# Wigglagotchi.net
KiCad netlist of a schematic drawn in Altium Designer
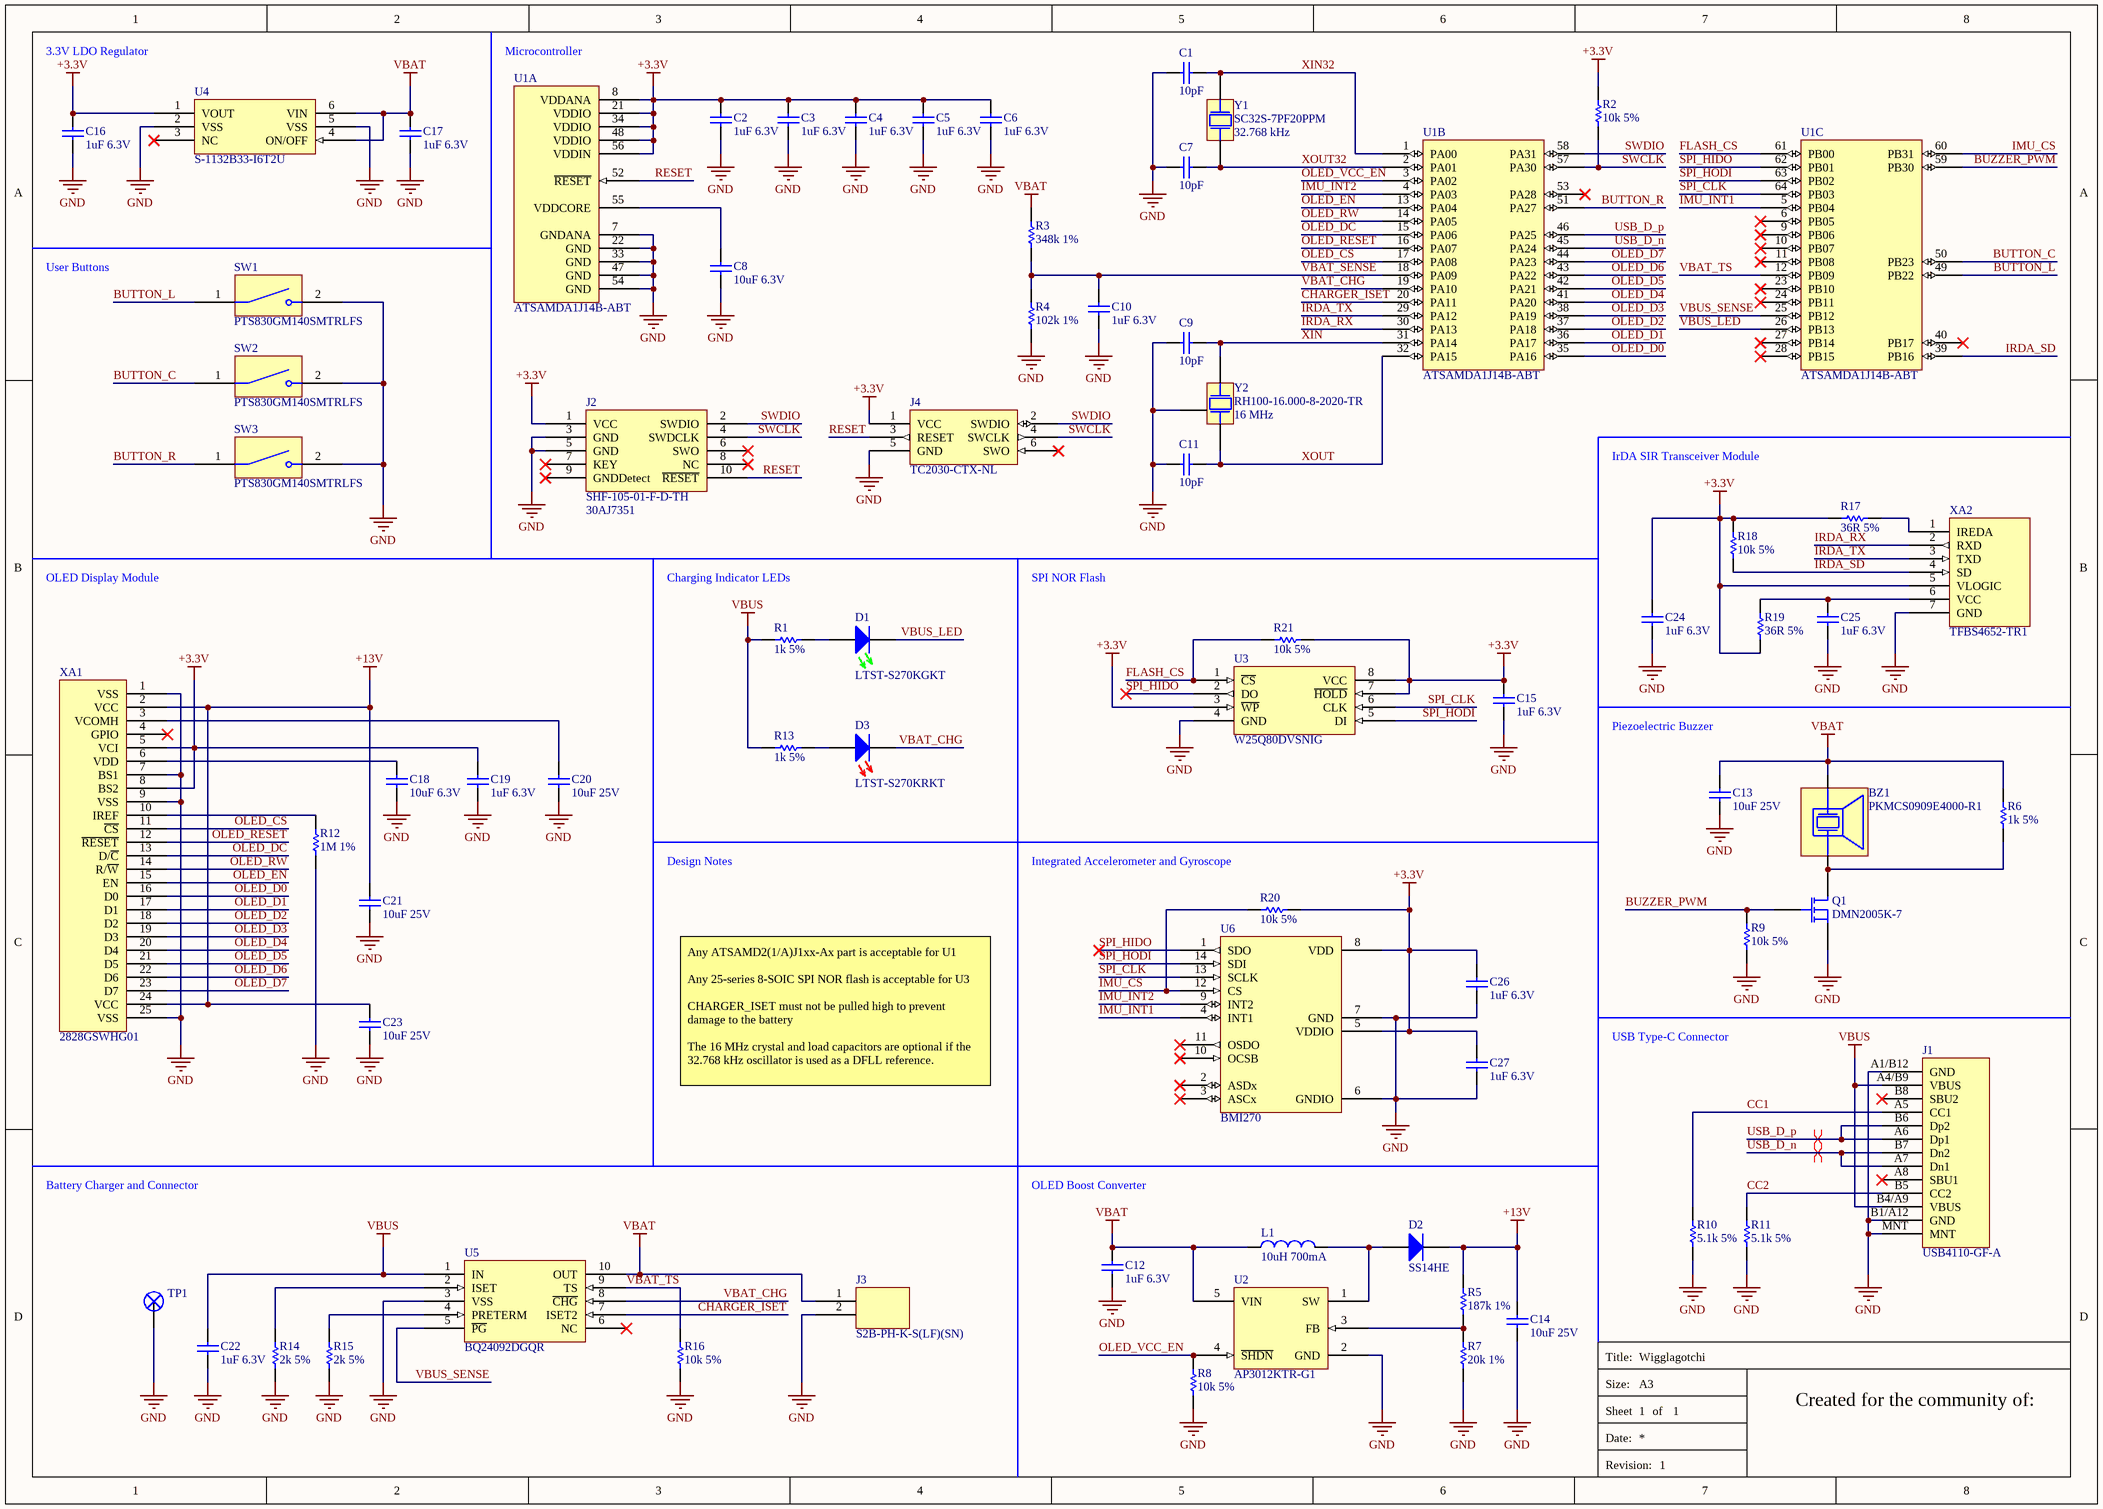
[diagram p0: Wigglagotchi.SchDoc]

(export (version "E")
  (design (tool "Eeschema 10.0.6"))
  (components
    (comp (ref "BZ1")
      (value "PKMCS0909E4000-R1")
      (footprint "PKMCS0909E4000-R1")
      (description "Buzzers Transducer, Externally Driven Piezo 1.5 V 4kHz 65dB @ 1.5V, 10cm Surface Mount Solder Pads")
      (libsource (lib "symbols") (part "PKMCS0909E4000-R1"))
    )
    (comp (ref "C1")
      (value "10pF")
      (footprint "GRM155 0402 Capacitor")
      (description "10 pF ±2% 50V Ceramic Capacitor C0G, NP0 0402 (1005 Metric)")
      (fields (field (name "Comment") "GCM1555C1H100GA16D"))
      (libsource (lib "symbols") (part "GCM1555C1H100GA16D"))
    )
    (comp (ref "C2")
      (value "1uF 6.3V")
      (footprint "GRM155 0402 Capacitor")
      (description "1 µF ±20% 6.3V Ceramic Capacitor X5R 0402 (1005 Metric)")
      (fields (field (name "Comment") "GRM153R60J105ME15D"))
      (libsource (lib "symbols") (part "GRM153R60J105ME15D"))
    )
    (comp (ref "C3")
      (value "1uF 6.3V")
      (footprint "GRM155 0402 Capacitor")
      (description "1 µF ±20% 6.3V Ceramic Capacitor X5R 0402 (1005 Metric)")
      (fields (field (name "Comment") "GRM153R60J105ME15D"))
      (libsource (lib "symbols") (part "GRM153R60J105ME15D"))
    )
    (comp (ref "C4")
      (value "1uF 6.3V")
      (footprint "GRM155 0402 Capacitor")
      (description "1 µF ±20% 6.3V Ceramic Capacitor X5R 0402 (1005 Metric)")
      (fields (field (name "Comment") "GRM153R60J105ME15D"))
      (libsource (lib "symbols") (part "GRM153R60J105ME15D"))
    )
    (comp (ref "C5")
      (value "1uF 6.3V")
      (footprint "GRM155 0402 Capacitor")
      (description "1 µF ±20% 6.3V Ceramic Capacitor X5R 0402 (1005 Metric)")
      (fields (field (name "Comment") "GRM153R60J105ME15D"))
      (libsource (lib "symbols") (part "GRM153R60J105ME15D"))
    )
    (comp (ref "C6")
      (value "1uF 6.3V")
      (footprint "GRM155 0402 Capacitor")
      (description "1 µF ±20% 6.3V Ceramic Capacitor X5R 0402 (1005 Metric)")
      (fields (field (name "Comment") "GRM153R60J105ME15D"))
      (libsource (lib "symbols") (part "GRM153R60J105ME15D"))
    )
    (comp (ref "C7")
      (value "10pF")
      (footprint "GRM155 0402 Capacitor")
      (description "10 pF ±2% 50V Ceramic Capacitor C0G, NP0 0402 (1005 Metric)")
      (fields (field (name "Comment") "GCM1555C1H100GA16D"))
      (libsource (lib "symbols") (part "GCM1555C1H100GA16D"))
    )
    (comp (ref "C8")
      (value "10uF 6.3V")
      (footprint "GRM155 0402 Capacitor")
      (description "10 µF ±20% 6.3V Ceramic Capacitor X5R 0402 (1005 Metric)")
      (fields (field (name "Comment") "GRM155R60J106ME15D"))
      (libsource (lib "symbols") (part "GRM155R60J106ME15D"))
    )
    (comp (ref "C9")
      (value "10pF")
      (footprint "GRM155 0402 Capacitor")
      (description "10 pF ±2% 50V Ceramic Capacitor C0G, NP0 0402 (1005 Metric)")
      (fields (field (name "Comment") "GCM1555C1H100GA16D"))
      (libsource (lib "symbols") (part "GCM1555C1H100GA16D"))
    )
    (comp (ref "C10")
      (value "1uF 6.3V")
      (footprint "GRM155 0402 Capacitor")
      (description "1 µF ±20% 6.3V Ceramic Capacitor X5R 0402 (1005 Metric)")
      (fields (field (name "Comment") "GRM153R60J105ME15D"))
      (libsource (lib "symbols") (part "GRM153R60J105ME15D"))
    )
    (comp (ref "C11")
      (value "10pF")
      (footprint "GRM155 0402 Capacitor")
      (description "10 pF ±2% 50V Ceramic Capacitor C0G, NP0 0402 (1005 Metric)")
      (fields (field (name "Comment") "GCM1555C1H100GA16D"))
      (libsource (lib "symbols") (part "GCM1555C1H100GA16D"))
    )
    (comp (ref "C12")
      (value "1uF 6.3V")
      (footprint "GRM155 0402 Capacitor")
      (description "1 µF ±20% 6.3V Ceramic Capacitor X5R 0402 (1005 Metric)")
      (fields (field (name "Comment") "GRM153R60J105ME15D"))
      (libsource (lib "symbols") (part "GRM153R60J105ME15D"))
    )
    (comp (ref "C13")
      (value "10uF 25V")
      (footprint "GRM21 0805 Capacitor")
      (description "10 µF ±10% 25V Ceramic Capacitor X5R 0805 (2012 Metric)")
      (fields (field (name "Comment") "GRM21BR61E106KA73K"))
      (libsource (lib "symbols") (part "GRM21BR61E106KA73K"))
    )
    (comp (ref "C14")
      (value "10uF 25V")
      (footprint "GRM21 0805 Capacitor")
      (description "10 µF ±10% 25V Ceramic Capacitor X5R 0805 (2012 Metric)")
      (fields (field (name "Comment") "GRM21BR61E106KA73K"))
      (libsource (lib "symbols") (part "GRM21BR61E106KA73K"))
    )
    (comp (ref "C15")
      (value "1uF 6.3V")
      (footprint "GRM155 0402 Capacitor")
      (description "1 µF ±20% 6.3V Ceramic Capacitor X5R 0402 (1005 Metric)")
      (fields (field (name "Comment") "GRM153R60J105ME15D"))
      (libsource (lib "symbols") (part "GRM153R60J105ME15D"))
    )
    (comp (ref "C16")
      (value "1uF 6.3V")
      (footprint "GRM155 0402 Capacitor")
      (description "1 µF ±20% 6.3V Ceramic Capacitor X5R 0402 (1005 Metric)")
      (fields (field (name "Comment") "GRM153R60J105ME15D"))
      (libsource (lib "symbols") (part "GRM153R60J105ME15D"))
    )
    (comp (ref "C17")
      (value "1uF 6.3V")
      (footprint "GRM155 0402 Capacitor")
      (description "1 µF ±20% 6.3V Ceramic Capacitor X5R 0402 (1005 Metric)")
      (fields (field (name "Comment") "GRM153R60J105ME15D"))
      (libsource (lib "symbols") (part "GRM153R60J105ME15D"))
    )
    (comp (ref "C18")
      (value "10uF 6.3V")
      (footprint "GRM155 0402 Capacitor")
      (description "10 µF ±20% 6.3V Ceramic Capacitor X5R 0402 (1005 Metric)")
      (fields (field (name "Comment") "GRM155R60J106ME15D"))
      (libsource (lib "symbols") (part "GRM155R60J106ME15D"))
    )
    (comp (ref "C19")
      (value "1uF 6.3V")
      (footprint "GRM155 0402 Capacitor")
      (description "1 µF ±20% 6.3V Ceramic Capacitor X5R 0402 (1005 Metric)")
      (fields (field (name "Comment") "GRM153R60J105ME15D"))
      (libsource (lib "symbols") (part "GRM153R60J105ME15D"))
    )
    (comp (ref "C20")
      (value "10uF 25V")
      (footprint "GRM21 0805 Capacitor")
      (description "10 µF ±10% 25V Ceramic Capacitor X5R 0805 (2012 Metric)")
      (fields (field (name "Comment") "GRM21BR61E106KA73K"))
      (libsource (lib "symbols") (part "GRM21BR61E106KA73K"))
    )
    (comp (ref "C21")
      (value "10uF 25V")
      (footprint "GRM21 0805 Capacitor")
      (description "10 µF ±10% 25V Ceramic Capacitor X5R 0805 (2012 Metric)")
      (fields (field (name "Comment") "GRM21BR61E106KA73K"))
      (libsource (lib "symbols") (part "GRM21BR61E106KA73K"))
    )
    (comp (ref "C22")
      (value "1uF 6.3V")
      (footprint "GRM155 0402 Capacitor")
      (description "1 µF ±20% 6.3V Ceramic Capacitor X5R 0402 (1005 Metric)")
      (fields (field (name "Comment") "GRM153R60J105ME15D"))
      (libsource (lib "symbols") (part "GRM153R60J105ME15D"))
    )
    (comp (ref "C23")
      (value "10uF 25V")
      (footprint "GRM21 0805 Capacitor")
      (description "10 µF ±10% 25V Ceramic Capacitor X5R 0805 (2012 Metric)")
      (fields (field (name "Comment") "GRM21BR61E106KA73K"))
      (libsource (lib "symbols") (part "GRM21BR61E106KA73K"))
    )
    (comp (ref "C24")
      (value "1uF 6.3V")
      (footprint "GRM155 0402 Capacitor")
      (description "1 µF ±20% 6.3V Ceramic Capacitor X5R 0402 (1005 Metric)")
      (fields (field (name "Comment") "GRM153R60J105ME15D"))
      (libsource (lib "symbols") (part "GRM153R60J105ME15D"))
    )
    (comp (ref "C25")
      (value "1uF 6.3V")
      (footprint "GRM155 0402 Capacitor")
      (description "1 µF ±20% 6.3V Ceramic Capacitor X5R 0402 (1005 Metric)")
      (fields (field (name "Comment") "GRM153R60J105ME15D"))
      (libsource (lib "symbols") (part "GRM153R60J105ME15D"))
    )
    (comp (ref "C26")
      (value "1uF 6.3V")
      (footprint "GRM155 0402 Capacitor")
      (description "1 µF ±20% 6.3V Ceramic Capacitor X5R 0402 (1005 Metric)")
      (fields (field (name "Comment") "GRM153R60J105ME15D"))
      (libsource (lib "symbols") (part "GRM153R60J105ME15D"))
    )
    (comp (ref "C27")
      (value "1uF 6.3V")
      (footprint "GRM155 0402 Capacitor")
      (description "1 µF ±20% 6.3V Ceramic Capacitor X5R 0402 (1005 Metric)")
      (fields (field (name "Comment") "GRM153R60J105ME15D"))
      (libsource (lib "symbols") (part "GRM153R60J105ME15D"))
    )
    (comp (ref "D1")
      (value "LTST-S270KGKT")
      (footprint "LTST-S270KRKT")
      (description "Green 571nm LED Indication - Discrete 2V 0603 (1608 Metric)")
      (libsource (lib "symbols") (part "LTST-S270KGKT"))
    )
    (comp (ref "D2")
      (value "SS14HE")
      (footprint "SS14HE")
      (description "Diode Schottky 40 V 1A Surface Mount SOD-323HE")
      (libsource (lib "symbols") (part "SS14HE"))
    )
    (comp (ref "D3")
      (value "LTST-S270KRKT")
      (footprint "LTST-S270KRKT")
      (description "Red 631nm LED Indication - Discrete 2V 0603 (1608 Metric)")
      (libsource (lib "symbols") (part "LTST-S270KRKT"))
    )
    (comp (ref "J1")
      (value "USB4110-GF-A")
      (footprint "USB4110-GF-A")
      (libsource (lib "symbols") (part "USB4110-GF-A"))
    )
    (comp (ref "J2")
      (value "SHF-105-01-F-D-TH")
      (footprint "SHF-105-01-F-D-TH")
      (description "Connector Header Through Hole 10 position 0.050\" (1.27mm)")
      (fields (field (name "SUPPLIER PART NUMBER 1") "30AJ7351"))
      (libsource (lib "symbols") (part "SHF-105-01-F-D-TH"))
    )
    (comp (ref "J3")
      (value "S2B-PH-K-S(LF)(SN)")
      (footprint "S2B-PH-K-S(LF)(SN)")
      (description "Connector Header Through Hole, Right Angle 2 position 0.079\" (2.00mm)")
      (libsource (lib "symbols") (part "S2B-PH-K-S(LF)(SN)"))
    )
    (comp (ref "J4")
      (value "TC2030-CTX-NL")
      (footprint "TC2030-CTX-NL")
      (description "6-Pin “No Legs” Cable with 10-pin micro-connector for Cortex processors")
      (libsource (lib "symbols") (part "TC2030-CTX-NL"))
    )
    (comp (ref "L1")
      (value "10uH 700mA")
      (footprint "BRL3225T100K")
      (description "10 µH Unshielded Drum Core, Wirewound Inductor 700 mA 420mOhm Max 1210 (3225 Metric)")
      (fields (field (name "Comment") "BRL3225T100K"))
      (libsource (lib "symbols") (part "BRL3225T100K"))
    )
    (comp (ref "Q1")
      (value "DMN2005K-7")
      (footprint "DMN2005K-7")
      (description "N-Channel 20 V 300mA (Ta) 350mW (Ta) Surface Mount SOT-23-3")
      (libsource (lib "symbols") (part "DMN2005K-7"))
    )
    (comp (ref "R1")
      (value "1k 5%")
      (footprint "RMCF0402 Resistor Package")
      (description "1 kOhms ±5% 0.063W, 1/16W Chip Resistor 0402 (1005 Metric) Automotive AEC-Q200 Thick Film")
      (fields (field (name "Comment") "RMCF0402JT1K00"))
      (libsource (lib "symbols") (part "RMCF0402JT1K00"))
    )
    (comp (ref "R2")
      (value "10k 5%")
      (footprint "RMCF0402 Resistor Package")
      (description "10 kOhms ±5% 0.063W, 1/16W Chip Resistor 0402 (1005 Metric) Automotive AEC-Q200 Thick Film")
      (fields (field (name "Comment") "RMCF0402JT10K0"))
      (libsource (lib "symbols") (part "RMCF0402JT10K0"))
    )
    (comp (ref "R3")
      (value "348k 1%")
      (footprint "RMCF0402 Resistor Package")
      (description "348 kOhms ±1% 0.063W, 1/16W Chip Resistor 0402 (1005 Metric) Automotive AEC-Q200 Thick Film")
      (fields (field (name "Comment") "RMCF0402FT348K"))
      (libsource (lib "symbols") (part "RMCF0402FT348K"))
    )
    (comp (ref "R4")
      (value "102k 1%")
      (footprint "RMCF0402 Resistor Package")
      (description "102 kOhms ±1% 0.063W, 1/16W Chip Resistor 0402 (1005 Metric) Automotive AEC-Q200 Thick Film")
      (fields (field (name "Comment") "RMCF0402FT102K"))
      (libsource (lib "symbols") (part "RMCF0402FT102K"))
    )
    (comp (ref "R5")
      (value "187k 1%")
      (footprint "RMCF0402 Resistor Package")
      (description "187 kOhms ±1% 0.063W, 1/16W Chip Resistor 0402 (1005 Metric) Automotive AEC-Q200 Thick Film")
      (fields (field (name "Comment") "RMCF0402FT187K"))
      (libsource (lib "symbols") (part "RMCF0402FT187K"))
    )
    (comp (ref "R6")
      (value "1k 5%")
      (footprint "RMCF0402 Resistor Package")
      (description "1 kOhms ±5% 0.063W, 1/16W Chip Resistor 0402 (1005 Metric) Automotive AEC-Q200 Thick Film")
      (fields (field (name "Comment") "RMCF0402JT1K00"))
      (libsource (lib "symbols") (part "RMCF0402JT1K00"))
    )
    (comp (ref "R7")
      (value "20k 1%")
      (footprint "RMCF0402 Resistor Package")
      (description "20 kOhms ±1% 0.063W, 1/16W Chip Resistor 0402 (1005 Metric) Automotive AEC-Q200 Thick Film")
      (fields (field (name "Comment") "RMCF0402FT20K0"))
      (libsource (lib "symbols") (part "RMCF0402FT20K0"))
    )
    (comp (ref "R8")
      (value "10k 5%")
      (footprint "RMCF0402 Resistor Package")
      (description "10 kOhms ±5% 0.063W, 1/16W Chip Resistor 0402 (1005 Metric) Automotive AEC-Q200 Thick Film")
      (fields (field (name "Comment") "RMCF0402JT10K0"))
      (libsource (lib "symbols") (part "RMCF0402JT10K0"))
    )
    (comp (ref "R9")
      (value "10k 5%")
      (footprint "RMCF0402 Resistor Package")
      (description "10 kOhms ±5% 0.063W, 1/16W Chip Resistor 0402 (1005 Metric) Automotive AEC-Q200 Thick Film")
      (fields (field (name "Comment") "RMCF0402JT10K0"))
      (libsource (lib "symbols") (part "RMCF0402JT10K0"))
    )
    (comp (ref "R10")
      (value "5.1k 5%")
      (footprint "RMCF0402 Resistor Package")
      (description "5.1 kOhms ±5% 0.063W, 1/16W Chip Resistor 0402 (1005 Metric) Automotive AEC-Q200 Thick Film")
      (fields (field (name "Comment") "RMCF0402JT5K10"))
      (libsource (lib "symbols") (part "RMCF0402JT5K10"))
    )
    (comp (ref "R11")
      (value "5.1k 5%")
      (footprint "RMCF0402 Resistor Package")
      (description "5.1 kOhms ±5% 0.063W, 1/16W Chip Resistor 0402 (1005 Metric) Automotive AEC-Q200 Thick Film")
      (fields (field (name "Comment") "RMCF0402JT5K10"))
      (libsource (lib "symbols") (part "RMCF0402JT5K10"))
    )
    (comp (ref "R12")
      (value "1M 1%")
      (footprint "RMCF0402 Resistor Package")
      (description "1 MOhms ±1% 0.063W, 1/16W Chip Resistor 0402 (1005 Metric) Automotive AEC-Q200 Thick Film")
      (fields (field (name "Comment") "RMCF0402FT1M00"))
      (libsource (lib "symbols") (part "RMCF0402FT1M00"))
    )
    (comp (ref "R13")
      (value "1k 5%")
      (footprint "RMCF0402 Resistor Package")
      (description "1 kOhms ±5% 0.063W, 1/16W Chip Resistor 0402 (1005 Metric) Automotive AEC-Q200 Thick Film")
      (fields (field (name "Comment") "RMCF0402JT1K00"))
      (libsource (lib "symbols") (part "RMCF0402JT1K00"))
    )
    (comp (ref "R14")
      (value "2k 5%")
      (footprint "RMCF0402 Resistor Package")
      (description "2 kOhms ±5% 0.063W, 1/16W Chip Resistor 0402 (1005 Metric) Automotive AEC-Q200 Thick Film")
      (fields (field (name "Comment") "RMCF0402JT2K00"))
      (libsource (lib "symbols") (part "RMCF0402JT2K00"))
    )
    (comp (ref "R15")
      (value "2k 5%")
      (footprint "RMCF0402 Resistor Package")
      (description "2 kOhms ±5% 0.063W, 1/16W Chip Resistor 0402 (1005 Metric) Automotive AEC-Q200 Thick Film")
      (fields (field (name "Comment") "RMCF0402JT2K00"))
      (libsource (lib "symbols") (part "RMCF0402JT2K00"))
    )
    (comp (ref "R16")
      (value "10k 5%")
      (footprint "RMCF0402 Resistor Package")
      (description "10 kOhms ±5% 0.063W, 1/16W Chip Resistor 0402 (1005 Metric) Automotive AEC-Q200 Thick Film")
      (fields (field (name "Comment") "RMCF0402JT10K0"))
      (libsource (lib "symbols") (part "RMCF0402JT10K0"))
    )
    (comp (ref "R17")
      (value "36R 5%")
      (footprint "RMCF0402 Resistor Package")
      (description "36 Ohms ±5% 0.063W, 1/16W Chip Resistor 0402 (1005 Metric) Automotive AEC-Q200 Thick Film")
      (fields (field (name "Comment") "RMCF0402JT36R0"))
      (libsource (lib "symbols") (part "RMCF0402JT36R0"))
    )
    (comp (ref "R18")
      (value "10k 5%")
      (footprint "RMCF0402 Resistor Package")
      (description "10 kOhms ±5% 0.063W, 1/16W Chip Resistor 0402 (1005 Metric) Automotive AEC-Q200 Thick Film")
      (fields (field (name "Comment") "RMCF0402JT10K0"))
      (libsource (lib "symbols") (part "RMCF0402JT10K0"))
    )
    (comp (ref "R19")
      (value "36R 5%")
      (footprint "RMCF0402 Resistor Package")
      (description "36 Ohms ±5% 0.063W, 1/16W Chip Resistor 0402 (1005 Metric) Automotive AEC-Q200 Thick Film")
      (fields (field (name "Comment") "RMCF0402JT36R0"))
      (libsource (lib "symbols") (part "RMCF0402JT36R0"))
    )
    (comp (ref "R20")
      (value "10k 5%")
      (footprint "RMCF0402 Resistor Package")
      (description "10 kOhms ±5% 0.063W, 1/16W Chip Resistor 0402 (1005 Metric) Automotive AEC-Q200 Thick Film")
      (fields (field (name "Comment") "RMCF0402JT10K0"))
      (libsource (lib "symbols") (part "RMCF0402JT10K0"))
    )
    (comp (ref "R21")
      (value "10k 5%")
      (footprint "RMCF0402 Resistor Package")
      (description "10 kOhms ±5% 0.063W, 1/16W Chip Resistor 0402 (1005 Metric) Automotive AEC-Q200 Thick Film")
      (fields (field (name "Comment") "RMCF0402JT10K0"))
      (libsource (lib "symbols") (part "RMCF0402JT10K0"))
    )
    (comp (ref "SW1")
      (value "PTS830GM140SMTRLFS")
      (footprint "PTS830GM140SMTRLFS")
      (description "Tactile Switch SPST-NO Top Actuated Surface Mount")
      (libsource (lib "symbols") (part "PTS830GM140SMTRLFS"))
    )
    (comp (ref "SW2")
      (value "PTS830GM140SMTRLFS")
      (footprint "PTS830GM140SMTRLFS")
      (description "Tactile Switch SPST-NO Top Actuated Surface Mount")
      (libsource (lib "symbols") (part "PTS830GM140SMTRLFS"))
    )
    (comp (ref "SW3")
      (value "PTS830GM140SMTRLFS")
      (footprint "PTS830GM140SMTRLFS")
      (description "Tactile Switch SPST-NO Top Actuated Surface Mount")
      (libsource (lib "symbols") (part "PTS830GM140SMTRLFS"))
    )
    (comp (ref "TP1")
      (value "5019")
      (footprint "5019 Test Point")
      (description "PC Test Point, Miniature Phosphor Bronze Silver Plating Surface Mount Mounting Type")
      (libsource (lib "symbols") (part "5019"))
    )
    (comp (ref "U1")
      (value "ATSAMDA1J14B-ABT")
      (footprint "ATSAMDA1J15B-ABT")
      (libsource (lib "symbols") (part "ATSAMDA1J14B-ABT"))
    )
    (comp (ref "U2")
      (value "AP3012KTR-G1")
      (footprint "AP3012KTR-G1")
      (description "Boost Switching Regulator IC Positive Adjustable 1.25V 1 Output 500mA (Switch) SC-74A, SOT-753")
      (libsource (lib "symbols") (part "AP3012KTR-G1"))
    )
    (comp (ref "U3")
      (value "W25Q80DVSNIG")
      (footprint "W25Q80DVSNIG")
      (description "FLASH - NOR Memory IC 8Mb (1M x 8) SPI - Quad I/O 104 MHz 8-SOIC")
      (libsource (lib "symbols") (part "W25Q80DVSNIG"))
    )
    (comp (ref "U4")
      (value "S-1132B33-I6T2U")
      (footprint "S-1132B33-I6T2U")
      (description "Linear Voltage Regulator IC Positive Fixed 1 Output 300mA SNT-6A")
      (libsource (lib "symbols") (part "S-1132B33-I6T2U"))
    )
    (comp (ref "U5")
      (value "BQ24092DGQR")
      (footprint "BQ24095DGQR")
      (description "Charger IC Lithium Ion/Polymer 10-HVSSOP")
      (libsource (lib "symbols") (part "BQ24092DGQR"))
    )
    (comp (ref "U6")
      (value "BMI270")
      (footprint "BMI270")
      (description "Accelerometer, Gyroscope, 6 Axis Sensor I²C, SPI Output")
      (libsource (lib "symbols") (part "BMI270"))
    )
    (comp (ref "XA1")
      (value "2828GSWHG01")
      (footprint "2828GSWHG01 OLED")
      (description "1.5 in. monochrome 128x128 OLED display module")
      (libsource (lib "symbols") (part "2828GSWHG01"))
    )
    (comp (ref "XA2")
      (value "TFBS4652-TR1")
      (footprint "TFBS4652-TR1")
      (description "115.2kbs (SIR) IRDA Transceiver Side View")
      (libsource (lib "symbols") (part "TFBS4652-TR1"))
    )
    (comp (ref "Y1")
      (value "SC32S-7PF20PPM")
      (footprint "SC32S-7PF20PPM")
      (description "32.768 kHz ±20ppm Crystal 7pF 70 kOhms 2-SMD, No Lead")
      (fields (field (name "ALTIUM_VALUE") "32.768 kHz"))
      (libsource (lib "symbols") (part "SC32S-7PF20PPM"))
    )
    (comp (ref "Y2")
      (value "RH100-16.000-8-2020-TR")
      (footprint "RH100-16.000-8-2020-TR")
      (description "16 MHz ±20ppm Crystal 8pF 70 Ohms 4-SMD, No Lead")
      (fields (field (name "ALTIUM_VALUE") "16 MHz"))
      (libsource (lib "symbols") (part "RH100-16.000-8-2020-TR"))
    )
  )
  (nets
    (net (code "1") (name "+3.3V") (class "Default")
      (node (ref "C15") (pin "2") (pinfunction "2_2") (pintype "passive"))
      (node (ref "C16") (pin "2") (pinfunction "2_2") (pintype "passive"))
      (node (ref "C19") (pin "2") (pinfunction "2_2") (pintype "passive"))
      (node (ref "C2") (pin "2") (pinfunction "2_2") (pintype "passive"))
      (node (ref "C24") (pin "2") (pinfunction "2_2") (pintype "passive"))
      (node (ref "C26") (pin "2") (pinfunction "2_2") (pintype "passive"))
      (node (ref "C27") (pin "2") (pinfunction "2_2") (pintype "passive"))
      (node (ref "C3") (pin "2") (pinfunction "2_2") (pintype "passive"))
      (node (ref "C4") (pin "2") (pinfunction "2_2") (pintype "passive"))
      (node (ref "C5") (pin "2") (pinfunction "2_2") (pintype "passive"))
      (node (ref "C6") (pin "2") (pinfunction "2_2") (pintype "passive"))
      (node (ref "J2") (pin "1") (pinfunction "VCC_1") (pintype "passive"))
      (node (ref "J4") (pin "1") (pinfunction "VCC_1") (pintype "power_in"))
      (node (ref "R17") (pin "1") (pinfunction "1_1") (pintype "passive"))
      (node (ref "R18") (pin "2") (pinfunction "2_2") (pintype "passive"))
      (node (ref "R19") (pin "1") (pinfunction "1_1") (pintype "passive"))
      (node (ref "R2") (pin "2") (pinfunction "2_2") (pintype "passive"))
      (node (ref "R20") (pin "1") (pinfunction "1_1") (pintype "passive"))
      (node (ref "R21") (pin "1") (pinfunction "1_1") (pintype "passive"))
      (node (ref "U1") (pin "21") (pinfunction "VDDIO_21") (pintype "power_in"))
      (node (ref "U1") (pin "34") (pinfunction "VDDIO_34") (pintype "power_in"))
      (node (ref "U1") (pin "48") (pinfunction "VDDIO_48") (pintype "power_in"))
      (node (ref "U1") (pin "56") (pinfunction "VDDIN_56") (pintype "power_in"))
      (node (ref "U1") (pin "8") (pinfunction "VDDANA_8") (pintype "power_in"))
      (node (ref "U3") (pin "3") (pinfunction "~{WP}_3") (pintype "input"))
      (node (ref "U3") (pin "7") (pinfunction "~{HOLD}_7") (pintype "input"))
      (node (ref "U3") (pin "8") (pinfunction "VCC_8") (pintype "power_in"))
      (node (ref "U4") (pin "1") (pinfunction "VOUT_1") (pintype "power_in"))
      (node (ref "U6") (pin "5") (pinfunction "VDDIO_5") (pintype "power_in"))
      (node (ref "U6") (pin "8") (pinfunction "VDD_8") (pintype "power_in"))
      (node (ref "XA1") (pin "5") (pinfunction "VCI_5") (pintype "passive"))
      (node (ref "XA1") (pin "8") (pinfunction "BS2_8") (pintype "passive"))
      (node (ref "XA2") (pin "5") (pinfunction "VLOGIC_5") (pintype "power_in"))
    )
    (net (code "2") (name "+13V") (class "Default")
      (node (ref "C14") (pin "2") (pinfunction "2_2") (pintype "passive"))
      (node (ref "C21") (pin "2") (pinfunction "2_2") (pintype "passive"))
      (node (ref "C23") (pin "2") (pinfunction "2_2") (pintype "passive"))
      (node (ref "D2") (pin "1") (pinfunction "1_1") (pintype "passive"))
      (node (ref "R5") (pin "2") (pinfunction "2_2") (pintype "passive"))
      (node (ref "XA1") (pin "2") (pinfunction "VCC_2") (pintype "passive"))
      (node (ref "XA1") (pin "24") (pinfunction "VCC_24") (pintype "passive"))
    )
    (net (code "3") (name "/BUTTON_C") (class "Default")
      (node (ref "SW2") (pin "1") (pintype "passive"))
      (node (ref "U1") (pin "50") (pinfunction "PB23_50") (pintype "bidirectional"))
    )
    (net (code "4") (name "/BUTTON_L") (class "Default")
      (node (ref "SW1") (pin "1") (pintype "passive"))
      (node (ref "U1") (pin "49") (pinfunction "PB22_49") (pintype "bidirectional"))
    )
    (net (code "5") (name "/BUTTON_R") (class "Default")
      (node (ref "SW3") (pin "1") (pintype "passive"))
      (node (ref "U1") (pin "51") (pinfunction "PA27_51") (pintype "bidirectional"))
    )
    (net (code "6") (name "/BUZZER_PWM") (class "Default")
      (node (ref "Q1") (pin "G") (pinfunction "G_G") (pintype "passive"))
      (node (ref "R9") (pin "2") (pinfunction "2_2") (pintype "passive"))
      (node (ref "U1") (pin "59") (pinfunction "PB30_59") (pintype "bidirectional"))
    )
    (net (code "7") (name "/CC1") (class "Default")
      (node (ref "J1") (pin "A5") (pinfunction "CC1_A5") (pintype "passive"))
      (node (ref "R10") (pin "2") (pinfunction "2_2") (pintype "passive"))
    )
    (net (code "8") (name "/CC2") (class "Default")
      (node (ref "J1") (pin "B5") (pinfunction "CC2_B5") (pintype "passive"))
      (node (ref "R11") (pin "2") (pinfunction "2_2") (pintype "passive"))
    )
    (net (code "9") (name "/CHARGER_ISET") (class "Default")
      (node (ref "U1") (pin "20") (pinfunction "PA11_20") (pintype "bidirectional"))
      (node (ref "U5") (pin "7") (pinfunction "ISET2_7") (pintype "input"))
    )
    (net (code "10") (name "/FLASH_CS") (class "Default")
      (node (ref "R21") (pin "2") (pinfunction "2_2") (pintype "passive"))
      (node (ref "U1") (pin "61") (pinfunction "PB00_61") (pintype "bidirectional"))
      (node (ref "U3") (pin "1") (pinfunction "~{CS}_1") (pintype "input"))
    )
    (net (code "11") (name "/IMU_CS") (class "Default")
      (node (ref "R20") (pin "2") (pinfunction "2_2") (pintype "passive"))
      (node (ref "U1") (pin "60") (pinfunction "PB31_60") (pintype "bidirectional"))
      (node (ref "U6") (pin "12") (pinfunction "CS_12") (pintype "input"))
    )
    (net (code "12") (name "/IMU_INT1") (class "Default")
      (node (ref "U1") (pin "5") (pinfunction "PB04_5") (pintype "bidirectional"))
      (node (ref "U6") (pin "4") (pinfunction "INT1_4") (pintype "bidirectional"))
    )
    (net (code "13") (name "/IMU_INT2") (class "Default")
      (node (ref "U1") (pin "4") (pinfunction "PA03_4") (pintype "bidirectional"))
      (node (ref "U6") (pin "9") (pinfunction "INT2_9") (pintype "bidirectional"))
    )
    (net (code "14") (name "/IRDA_RX") (class "Default")
      (node (ref "U1") (pin "30") (pinfunction "PA13_30") (pintype "bidirectional"))
      (node (ref "XA2") (pin "2") (pinfunction "RXD_2") (pintype "output"))
    )
    (net (code "15") (name "/IRDA_SD") (class "Default")
      (node (ref "R18") (pin "1") (pinfunction "1_1") (pintype "passive"))
      (node (ref "U1") (pin "39") (pinfunction "PB16_39") (pintype "bidirectional"))
      (node (ref "XA2") (pin "4") (pinfunction "SD_4") (pintype "input"))
    )
    (net (code "16") (name "/IRDA_TX") (class "Default")
      (node (ref "U1") (pin "29") (pinfunction "PA12_29") (pintype "bidirectional"))
      (node (ref "XA2") (pin "3") (pinfunction "TXD_3") (pintype "input"))
    )
    (net (code "17") (name "/OLED_CS") (class "Default")
      (node (ref "U1") (pin "17") (pinfunction "PA08_17") (pintype "bidirectional"))
      (node (ref "XA1") (pin "11") (pinfunction "~{CS}_11") (pintype "passive"))
    )
    (net (code "18") (name "/OLED_D0") (class "Default")
      (node (ref "U1") (pin "35") (pinfunction "PA16_35") (pintype "bidirectional"))
      (node (ref "XA1") (pin "16") (pinfunction "D0_16") (pintype "passive"))
    )
    (net (code "19") (name "/OLED_D1") (class "Default")
      (node (ref "U1") (pin "36") (pinfunction "PA17_36") (pintype "bidirectional"))
      (node (ref "XA1") (pin "17") (pinfunction "D1_17") (pintype "passive"))
    )
    (net (code "20") (name "/OLED_D2") (class "Default")
      (node (ref "U1") (pin "37") (pinfunction "PA18_37") (pintype "bidirectional"))
      (node (ref "XA1") (pin "18") (pinfunction "D2_18") (pintype "passive"))
    )
    (net (code "21") (name "/OLED_D3") (class "Default")
      (node (ref "U1") (pin "38") (pinfunction "PA19_38") (pintype "bidirectional"))
      (node (ref "XA1") (pin "19") (pinfunction "D3_19") (pintype "passive"))
    )
    (net (code "22") (name "/OLED_D4") (class "Default")
      (node (ref "U1") (pin "41") (pinfunction "PA20_41") (pintype "bidirectional"))
      (node (ref "XA1") (pin "20") (pinfunction "D4_20") (pintype "passive"))
    )
    (net (code "23") (name "/OLED_D5") (class "Default")
      (node (ref "U1") (pin "42") (pinfunction "PA21_42") (pintype "bidirectional"))
      (node (ref "XA1") (pin "21") (pinfunction "D5_21") (pintype "passive"))
    )
    (net (code "24") (name "/OLED_D6") (class "Default")
      (node (ref "U1") (pin "43") (pinfunction "PA22_43") (pintype "bidirectional"))
      (node (ref "XA1") (pin "22") (pinfunction "D6_22") (pintype "passive"))
    )
    (net (code "25") (name "/OLED_D7") (class "Default")
      (node (ref "U1") (pin "44") (pinfunction "PA23_44") (pintype "bidirectional"))
      (node (ref "XA1") (pin "23") (pinfunction "D7_23") (pintype "passive"))
    )
    (net (code "26") (name "/OLED_DC") (class "Default")
      (node (ref "U1") (pin "15") (pinfunction "PA06_15") (pintype "bidirectional"))
      (node (ref "XA1") (pin "13") (pinfunction "D/~{C}_13") (pintype "passive"))
    )
    (net (code "27") (name "/OLED_EN") (class "Default")
      (node (ref "U1") (pin "13") (pinfunction "PA04_13") (pintype "bidirectional"))
      (node (ref "XA1") (pin "15") (pinfunction "EN_15") (pintype "passive"))
    )
    (net (code "28") (name "/OLED_RESET") (class "Default")
      (node (ref "U1") (pin "16") (pinfunction "PA07_16") (pintype "bidirectional"))
      (node (ref "XA1") (pin "12") (pinfunction "~{RESET}_12") (pintype "passive"))
    )
    (net (code "29") (name "/OLED_RW") (class "Default")
      (node (ref "U1") (pin "14") (pinfunction "PA05_14") (pintype "bidirectional"))
      (node (ref "XA1") (pin "14") (pinfunction "R/~{W}_14") (pintype "passive"))
    )
    (net (code "30") (name "/OLED_VCC_EN") (class "Default")
      (node (ref "R8") (pin "2") (pinfunction "2_2") (pintype "passive"))
      (node (ref "U1") (pin "3") (pinfunction "PA02_3") (pintype "bidirectional"))
      (node (ref "U2") (pin "4") (pinfunction "~{SHDN}_4") (pintype "input"))
    )
    (net (code "31") (name "/RESET") (class "Default")
      (node (ref "J2") (pin "10") (pinfunction "~{RESET}_10") (pintype "passive"))
      (node (ref "J4") (pin "3") (pinfunction "RESET_3") (pintype "output"))
      (node (ref "U1") (pin "52") (pinfunction "~{RESET}_52") (pintype "input"))
    )
    (net (code "32") (name "/SPI_CLK") (class "Default")
      (node (ref "U1") (pin "64") (pinfunction "PB03_64") (pintype "bidirectional"))
      (node (ref "U3") (pin "6") (pinfunction "CLK_6") (pintype "input"))
      (node (ref "U6") (pin "13") (pinfunction "SCLK_13") (pintype "input"))
    )
    (net (code "33") (name "/SPI_HIDO") (class "Default")
      (node (ref "U1") (pin "62") (pinfunction "PB01_62") (pintype "bidirectional"))
      (node (ref "U3") (pin "2") (pinfunction "DO_2") (pintype "output"))
      (node (ref "U6") (pin "1") (pinfunction "SDO_1") (pintype "output"))
    )
    (net (code "34") (name "/SPI_HODI") (class "Default")
      (node (ref "U1") (pin "63") (pinfunction "PB02_63") (pintype "bidirectional"))
      (node (ref "U3") (pin "5") (pinfunction "DI_5") (pintype "input"))
      (node (ref "U6") (pin "14") (pinfunction "SDI_14") (pintype "input"))
    )
    (net (code "35") (name "/SWCLK") (class "Default")
      (node (ref "J2") (pin "4") (pinfunction "SWDCLK_4") (pintype "passive"))
      (node (ref "J4") (pin "4") (pinfunction "SWCLK_4") (pintype "output"))
      (node (ref "R2") (pin "1") (pinfunction "1_1") (pintype "passive"))
      (node (ref "U1") (pin "57") (pinfunction "PA30_57") (pintype "bidirectional"))
    )
    (net (code "36") (name "/SWDIO") (class "Default")
      (node (ref "J2") (pin "2") (pinfunction "SWDIO_2") (pintype "passive"))
      (node (ref "J4") (pin "2") (pinfunction "SWDIO_2") (pintype "bidirectional"))
      (node (ref "U1") (pin "58") (pinfunction "PA31_58") (pintype "bidirectional"))
    )
    (net (code "37") (name "/USB_D_n") (class "Default")
      (node (ref "J1") (pin "A7") (pinfunction "Dn1_A7") (pintype "passive"))
      (node (ref "J1") (pin "B7") (pinfunction "Dn2_B7") (pintype "passive"))
      (node (ref "U1") (pin "45") (pinfunction "PA24_45") (pintype "bidirectional"))
    )
    (net (code "38") (name "/USB_D_p") (class "Default")
      (node (ref "J1") (pin "A6") (pinfunction "Dp1_A6") (pintype "passive"))
      (node (ref "J1") (pin "B6") (pinfunction "Dp2_B6") (pintype "passive"))
      (node (ref "U1") (pin "46") (pinfunction "PA25_46") (pintype "bidirectional"))
    )
    (net (code "39") (name "/VBAT_CHG") (class "Default")
      (node (ref "D3") (pin "1") (pinfunction "1_1") (pintype "passive"))
      (node (ref "U1") (pin "19") (pinfunction "PA10_19") (pintype "bidirectional"))
      (node (ref "U5") (pin "8") (pinfunction "~{CHG}_8") (pintype "input"))
    )
    (net (code "40") (name "/VBAT_SENSE") (class "Default")
      (node (ref "C10") (pin "2") (pinfunction "2_2") (pintype "passive"))
      (node (ref "R3") (pin "1") (pinfunction "1_1") (pintype "passive"))
      (node (ref "R4") (pin "2") (pinfunction "2_2") (pintype "passive"))
      (node (ref "U1") (pin "18") (pinfunction "PA09_18") (pintype "bidirectional"))
    )
    (net (code "41") (name "/VBAT_TS") (class "Default")
      (node (ref "R16") (pin "2") (pinfunction "2_2") (pintype "passive"))
      (node (ref "U1") (pin "12") (pinfunction "PB09_12") (pintype "bidirectional"))
      (node (ref "U5") (pin "9") (pinfunction "TS_9") (pintype "input"))
    )
    (net (code "42") (name "/VBUS_LED") (class "Default")
      (node (ref "D1") (pin "1") (pinfunction "1_1") (pintype "passive"))
      (node (ref "U1") (pin "26") (pinfunction "PB13_26") (pintype "bidirectional"))
    )
    (net (code "43") (name "/VBUS_SENSE") (class "Default")
      (node (ref "U1") (pin "25") (pinfunction "PB12_25") (pintype "bidirectional"))
      (node (ref "U5") (pin "5") (pinfunction "~{PG}_5") (pintype "open_collector"))
    )
    (net (code "44") (name "/XIN") (class "Default")
      (node (ref "C9") (pin "1") (pinfunction "1_1") (pintype "passive"))
      (node (ref "U1") (pin "31") (pinfunction "PA14_31") (pintype "bidirectional"))
      (node (ref "Y2") (pin "3") (pinfunction "X2_3") (pintype "passive"))
    )
    (net (code "45") (name "/XIN32") (class "Default")
      (node (ref "C1") (pin "1") (pinfunction "1_1") (pintype "passive"))
      (node (ref "U1") (pin "1") (pinfunction "PA00_1") (pintype "bidirectional"))
      (node (ref "Y1") (pin "2") (pinfunction "X2_2") (pintype "passive"))
    )
    (net (code "46") (name "/XOUT") (class "Default")
      (node (ref "C11") (pin "1") (pinfunction "1_1") (pintype "passive"))
      (node (ref "U1") (pin "32") (pinfunction "PA15_32") (pintype "bidirectional"))
      (node (ref "Y2") (pin "1") (pinfunction "X1_1") (pintype "passive"))
    )
    (net (code "47") (name "/XOUT32") (class "Default")
      (node (ref "C7") (pin "1") (pinfunction "1_1") (pintype "passive"))
      (node (ref "U1") (pin "2") (pinfunction "PA01_2") (pintype "bidirectional"))
      (node (ref "Y1") (pin "1") (pinfunction "X1_1") (pintype "passive"))
    )
    (net (code "48") (name "GND") (class "Default")
      (node (ref "C1") (pin "2") (pinfunction "2_2") (pintype "passive"))
      (node (ref "C10") (pin "1") (pinfunction "1_1") (pintype "passive"))
      (node (ref "C11") (pin "2") (pinfunction "2_2") (pintype "passive"))
      (node (ref "C12") (pin "1") (pinfunction "1_1") (pintype "passive"))
      (node (ref "C13") (pin "1") (pinfunction "1_1") (pintype "passive"))
      (node (ref "C14") (pin "1") (pinfunction "1_1") (pintype "passive"))
      (node (ref "C15") (pin "1") (pinfunction "1_1") (pintype "passive"))
      (node (ref "C16") (pin "1") (pinfunction "1_1") (pintype "passive"))
      (node (ref "C17") (pin "1") (pinfunction "1_1") (pintype "passive"))
      (node (ref "C18") (pin "1") (pinfunction "1_1") (pintype "passive"))
      (node (ref "C19") (pin "1") (pinfunction "1_1") (pintype "passive"))
      (node (ref "C2") (pin "1") (pinfunction "1_1") (pintype "passive"))
      (node (ref "C20") (pin "1") (pinfunction "1_1") (pintype "passive"))
      (node (ref "C21") (pin "1") (pinfunction "1_1") (pintype "passive"))
      (node (ref "C22") (pin "1") (pinfunction "1_1") (pintype "passive"))
      (node (ref "C23") (pin "1") (pinfunction "1_1") (pintype "passive"))
      (node (ref "C24") (pin "1") (pinfunction "1_1") (pintype "passive"))
      (node (ref "C25") (pin "1") (pinfunction "1_1") (pintype "passive"))
      (node (ref "C26") (pin "1") (pinfunction "1_1") (pintype "passive"))
      (node (ref "C27") (pin "1") (pinfunction "1_1") (pintype "passive"))
      (node (ref "C3") (pin "1") (pinfunction "1_1") (pintype "passive"))
      (node (ref "C4") (pin "1") (pinfunction "1_1") (pintype "passive"))
      (node (ref "C5") (pin "1") (pinfunction "1_1") (pintype "passive"))
      (node (ref "C6") (pin "1") (pinfunction "1_1") (pintype "passive"))
      (node (ref "C7") (pin "2") (pinfunction "2_2") (pintype "passive"))
      (node (ref "C8") (pin "1") (pinfunction "1_1") (pintype "passive"))
      (node (ref "C9") (pin "2") (pinfunction "2_2") (pintype "passive"))
      (node (ref "J1") (pin "A1/B12") (pinfunction "GND_A1/B12") (pintype "power_in"))
      (node (ref "J1") (pin "B1/A12") (pinfunction "GND_B1/A12") (pintype "power_in"))
      (node (ref "J1") (pin "MNT") (pinfunction "MNT_MNT") (pintype "passive"))
      (node (ref "J2") (pin "3") (pinfunction "GND_3") (pintype "passive"))
      (node (ref "J2") (pin "5") (pinfunction "GND_5") (pintype "passive"))
      (node (ref "J3") (pin "2") (pintype "passive"))
      (node (ref "J4") (pin "5") (pinfunction "GND_5") (pintype "power_in"))
      (node (ref "Q1") (pin "S") (pinfunction "S_S") (pintype "passive"))
      (node (ref "R10") (pin "1") (pinfunction "1_1") (pintype "passive"))
      (node (ref "R11") (pin "1") (pinfunction "1_1") (pintype "passive"))
      (node (ref "R12") (pin "1") (pinfunction "1_1") (pintype "passive"))
      (node (ref "R14") (pin "2") (pinfunction "2_2") (pintype "passive"))
      (node (ref "R15") (pin "1") (pinfunction "1_1") (pintype "passive"))
      (node (ref "R16") (pin "1") (pinfunction "1_1") (pintype "passive"))
      (node (ref "R4") (pin "1") (pinfunction "1_1") (pintype "passive"))
      (node (ref "R7") (pin "1") (pinfunction "1_1") (pintype "passive"))
      (node (ref "R8") (pin "1") (pinfunction "1_1") (pintype "passive"))
      (node (ref "R9") (pin "1") (pinfunction "1_1") (pintype "passive"))
      (node (ref "SW1") (pin "2") (pintype "passive"))
      (node (ref "SW2") (pin "2") (pintype "passive"))
      (node (ref "SW3") (pin "2") (pintype "passive"))
      (node (ref "TP1") (pin "1") (pinfunction "1_1") (pintype "passive"))
      (node (ref "U1") (pin "22") (pinfunction "GND_22") (pintype "power_in"))
      (node (ref "U1") (pin "33") (pinfunction "GND_33") (pintype "power_in"))
      (node (ref "U1") (pin "47") (pinfunction "GND_47") (pintype "power_in"))
      (node (ref "U1") (pin "54") (pinfunction "GND_54") (pintype "power_in"))
      (node (ref "U1") (pin "7") (pinfunction "GNDANA_7") (pintype "power_in"))
      (node (ref "U2") (pin "2") (pinfunction "GND_2") (pintype "power_in"))
      (node (ref "U3") (pin "4") (pinfunction "GND_4") (pintype "power_in"))
      (node (ref "U4") (pin "2") (pinfunction "VSS_2") (pintype "power_in"))
      (node (ref "U4") (pin "5") (pinfunction "VSS_5") (pintype "power_in"))
      (node (ref "U5") (pin "3") (pinfunction "VSS_3") (pintype "power_in"))
      (node (ref "U6") (pin "6") (pinfunction "GNDIO_6") (pintype "power_in"))
      (node (ref "U6") (pin "7") (pinfunction "GND_7") (pintype "power_in"))
      (node (ref "XA1") (pin "1") (pinfunction "VSS_1") (pintype "passive"))
      (node (ref "XA1") (pin "25") (pinfunction "VSS_25") (pintype "passive"))
      (node (ref "XA1") (pin "7") (pinfunction "BS1_7") (pintype "passive"))
      (node (ref "XA1") (pin "9") (pinfunction "VSS_9") (pintype "passive"))
      (node (ref "XA2") (pin "7") (pinfunction "GND_7") (pintype "power_in"))
      (node (ref "Y2") (pin "2") (pinfunction "GND_2") (pintype "passive"))
    )
    (net (code "49") (name "Net-(BZ1-Pad2)") (class "Default")
      (node (ref "BZ1") (pin "2") (pinfunction "2_2") (pintype "passive"))
      (node (ref "Q1") (pin "D") (pinfunction "D_D") (pintype "passive"))
      (node (ref "R6") (pin "1") (pinfunction "1_1") (pintype "passive"))
    )
    (net (code "50") (name "Net-(D1-Pad2)") (class "Default")
      (node (ref "D1") (pin "2") (pinfunction "2_2") (pintype "passive"))
      (node (ref "R1") (pin "1") (pinfunction "1_1") (pintype "passive"))
    )
    (net (code "51") (name "Net-(D3-Pad2)") (class "Default")
      (node (ref "D3") (pin "2") (pinfunction "2_2") (pintype "passive"))
      (node (ref "R13") (pin "1") (pinfunction "1_1") (pintype "passive"))
    )
    (net (code "52") (name "Net-(U1A-VDDCORE)") (class "Default")
      (node (ref "C8") (pin "2") (pinfunction "2_2") (pintype "passive"))
      (node (ref "U1") (pin "55") (pinfunction "VDDCORE_55") (pintype "power_in"))
    )
    (net (code "53") (name "Net-(U2-FB)") (class "Default")
      (node (ref "R5") (pin "1") (pinfunction "1_1") (pintype "passive"))
      (node (ref "R7") (pin "2") (pinfunction "2_2") (pintype "passive"))
      (node (ref "U2") (pin "3") (pinfunction "FB_3") (pintype "input"))
    )
    (net (code "54") (name "Net-(U2-SW)") (class "Default")
      (node (ref "D2") (pin "2") (pinfunction "2_2") (pintype "passive"))
      (node (ref "L1") (pin "2") (pinfunction "2_2") (pintype "passive"))
      (node (ref "U2") (pin "1") (pinfunction "SW_1") (pintype "power_in"))
    )
    (net (code "55") (name "Net-(U5-ISET)") (class "Default")
      (node (ref "R14") (pin "1") (pinfunction "1_1") (pintype "passive"))
      (node (ref "U5") (pin "2") (pinfunction "ISET_2") (pintype "input"))
    )
    (net (code "56") (name "Net-(U5-PRETERM)") (class "Default")
      (node (ref "R15") (pin "2") (pinfunction "2_2") (pintype "passive"))
      (node (ref "U5") (pin "4") (pinfunction "PRETERM_4") (pintype "input"))
    )
    (net (code "57") (name "Net-(XA1-IREF)") (class "Default")
      (node (ref "R12") (pin "2") (pinfunction "2_2") (pintype "passive"))
      (node (ref "XA1") (pin "10") (pinfunction "IREF_10") (pintype "passive"))
    )
    (net (code "58") (name "Net-(XA1-VCOMH)") (class "Default")
      (node (ref "C20") (pin "2") (pinfunction "2_2") (pintype "passive"))
      (node (ref "XA1") (pin "3") (pinfunction "VCOMH_3") (pintype "passive"))
    )
    (net (code "59") (name "Net-(XA1-VDD)") (class "Default")
      (node (ref "C18") (pin "2") (pinfunction "2_2") (pintype "passive"))
      (node (ref "XA1") (pin "6") (pinfunction "VDD_6") (pintype "passive"))
    )
    (net (code "60") (name "Net-(XA2-IREDA)") (class "Default")
      (node (ref "R17") (pin "2") (pinfunction "2_2") (pintype "passive"))
      (node (ref "XA2") (pin "1") (pinfunction "IREDA_1") (pintype "passive"))
    )
    (net (code "61") (name "Net-(XA2-VCC)") (class "Default")
      (node (ref "C25") (pin "2") (pinfunction "2_2") (pintype "passive"))
      (node (ref "R19") (pin "2") (pinfunction "2_2") (pintype "passive"))
      (node (ref "XA2") (pin "6") (pinfunction "VCC_6") (pintype "power_in"))
    )
    (net (code "62") (name "VBAT") (class "Default")
      (node (ref "BZ1") (pin "1") (pinfunction "1_1") (pintype "passive"))
      (node (ref "C12") (pin "2") (pinfunction "2_2") (pintype "passive"))
      (node (ref "C13") (pin "2") (pinfunction "2_2") (pintype "passive"))
      (node (ref "C17") (pin "2") (pinfunction "2_2") (pintype "passive"))
      (node (ref "J3") (pin "1") (pintype "passive"))
      (node (ref "L1") (pin "1") (pinfunction "1_1") (pintype "passive"))
      (node (ref "R3") (pin "2") (pinfunction "2_2") (pintype "passive"))
      (node (ref "R6") (pin "2") (pinfunction "2_2") (pintype "passive"))
      (node (ref "U2") (pin "5") (pinfunction "VIN_5") (pintype "power_in"))
      (node (ref "U4") (pin "4") (pinfunction "ON/OFF_4") (pintype "input"))
      (node (ref "U4") (pin "6") (pinfunction "VIN_6") (pintype "power_in"))
      (node (ref "U5") (pin "10") (pinfunction "OUT_10") (pintype "power_in"))
    )
    (net (code "63") (name "VBUS") (class "Default")
      (node (ref "C22") (pin "2") (pinfunction "2_2") (pintype "passive"))
      (node (ref "J1") (pin "A4/B9") (pinfunction "VBUS_A4/B9") (pintype "power_in"))
      (node (ref "J1") (pin "B4/A9") (pinfunction "VBUS_B4/A9") (pintype "power_in"))
      (node (ref "R1") (pin "2") (pinfunction "2_2") (pintype "passive"))
      (node (ref "R13") (pin "2") (pinfunction "2_2") (pintype "passive"))
      (node (ref "U5") (pin "1") (pinfunction "IN_1") (pintype "power_in"))
    )
    (net (code "64") (name "unconnected-(J1-SBU1-PadA8)") (class "Default")
      (node (ref "J1") (pin "A8") (pinfunction "SBU1_A8") (pintype "passive+no_connect"))
    )
    (net (code "65") (name "unconnected-(J1-SBU2-PadB8)") (class "Default")
      (node (ref "J1") (pin "B8") (pinfunction "SBU2_B8") (pintype "passive+no_connect"))
    )
    (net (code "66") (name "unconnected-(J2-GNDDetect-Pad9)") (class "Default")
      (node (ref "J2") (pin "9") (pinfunction "GNDDetect_9") (pintype "passive+no_connect"))
    )
    (net (code "67") (name "unconnected-(J2-KEY-Pad7)") (class "Default")
      (node (ref "J2") (pin "7") (pinfunction "KEY_7") (pintype "passive+no_connect"))
    )
    (net (code "68") (name "unconnected-(J2-NC-Pad8)") (class "Default")
      (node (ref "J2") (pin "8") (pinfunction "NC_8") (pintype "passive+no_connect"))
    )
    (net (code "69") (name "unconnected-(J2-SWO-Pad6)") (class "Default")
      (node (ref "J2") (pin "6") (pinfunction "SWO_6") (pintype "passive+no_connect"))
    )
    (net (code "70") (name "unconnected-(J4-SWO-Pad6)") (class "Default")
      (node (ref "J4") (pin "6") (pinfunction "SWO_6") (pintype "input+no_connect"))
    )
    (net (code "71") (name "unconnected-(U1B-PA28-Pad53)") (class "Default")
      (node (ref "U1") (pin "53") (pinfunction "PA28_53") (pintype "bidirectional+no_connect"))
    )
    (net (code "72") (name "unconnected-(U1C-PB05-Pad6)") (class "Default")
      (node (ref "U1") (pin "6") (pinfunction "PB05_6") (pintype "bidirectional+no_connect"))
    )
    (net (code "73") (name "unconnected-(U1C-PB06-Pad9)") (class "Default")
      (node (ref "U1") (pin "9") (pinfunction "PB06_9") (pintype "bidirectional+no_connect"))
    )
    (net (code "74") (name "unconnected-(U1C-PB07-Pad10)") (class "Default")
      (node (ref "U1") (pin "10") (pinfunction "PB07_10") (pintype "bidirectional+no_connect"))
    )
    (net (code "75") (name "unconnected-(U1C-PB08-Pad11)") (class "Default")
      (node (ref "U1") (pin "11") (pinfunction "PB08_11") (pintype "bidirectional+no_connect"))
    )
    (net (code "76") (name "unconnected-(U1C-PB10-Pad23)") (class "Default")
      (node (ref "U1") (pin "23") (pinfunction "PB10_23") (pintype "bidirectional+no_connect"))
    )
    (net (code "77") (name "unconnected-(U1C-PB11-Pad24)") (class "Default")
      (node (ref "U1") (pin "24") (pinfunction "PB11_24") (pintype "bidirectional+no_connect"))
    )
    (net (code "78") (name "unconnected-(U1C-PB14-Pad27)") (class "Default")
      (node (ref "U1") (pin "27") (pinfunction "PB14_27") (pintype "bidirectional+no_connect"))
    )
    (net (code "79") (name "unconnected-(U1C-PB15-Pad28)") (class "Default")
      (node (ref "U1") (pin "28") (pinfunction "PB15_28") (pintype "bidirectional+no_connect"))
    )
    (net (code "80") (name "unconnected-(U1C-PB17-Pad40)") (class "Default")
      (node (ref "U1") (pin "40") (pinfunction "PB17_40") (pintype "bidirectional+no_connect"))
    )
    (net (code "81") (name "unconnected-(U4-NC-Pad3)") (class "Default")
      (node (ref "U4") (pin "3") (pinfunction "NC_3") (pintype "passive+no_connect"))
    )
    (net (code "82") (name "unconnected-(U5-NC-Pad6)") (class "Default")
      (node (ref "U5") (pin "6") (pinfunction "NC_6") (pintype "passive+no_connect"))
    )
    (net (code "83") (name "unconnected-(U6-ASCx-Pad3)") (class "Default")
      (node (ref "U6") (pin "3") (pinfunction "ASCx_3") (pintype "bidirectional+no_connect"))
    )
    (net (code "84") (name "unconnected-(U6-ASDx-Pad2)") (class "Default")
      (node (ref "U6") (pin "2") (pinfunction "ASDx_2") (pintype "bidirectional+no_connect"))
    )
    (net (code "85") (name "unconnected-(U6-OCSB-Pad10)") (class "Default")
      (node (ref "U6") (pin "10") (pinfunction "OCSB_10") (pintype "input+no_connect"))
    )
    (net (code "86") (name "unconnected-(U6-OSDO-Pad11)") (class "Default")
      (node (ref "U6") (pin "11") (pinfunction "OSDO_11") (pintype "output+no_connect"))
    )
    (net (code "87") (name "unconnected-(XA1-GPIO-Pad4)") (class "Default")
      (node (ref "XA1") (pin "4") (pinfunction "GPIO_4") (pintype "passive+no_connect"))
    )
  )
)
